# Sheet.net
KiCad netlist of a schematic drawn in Altium Designer
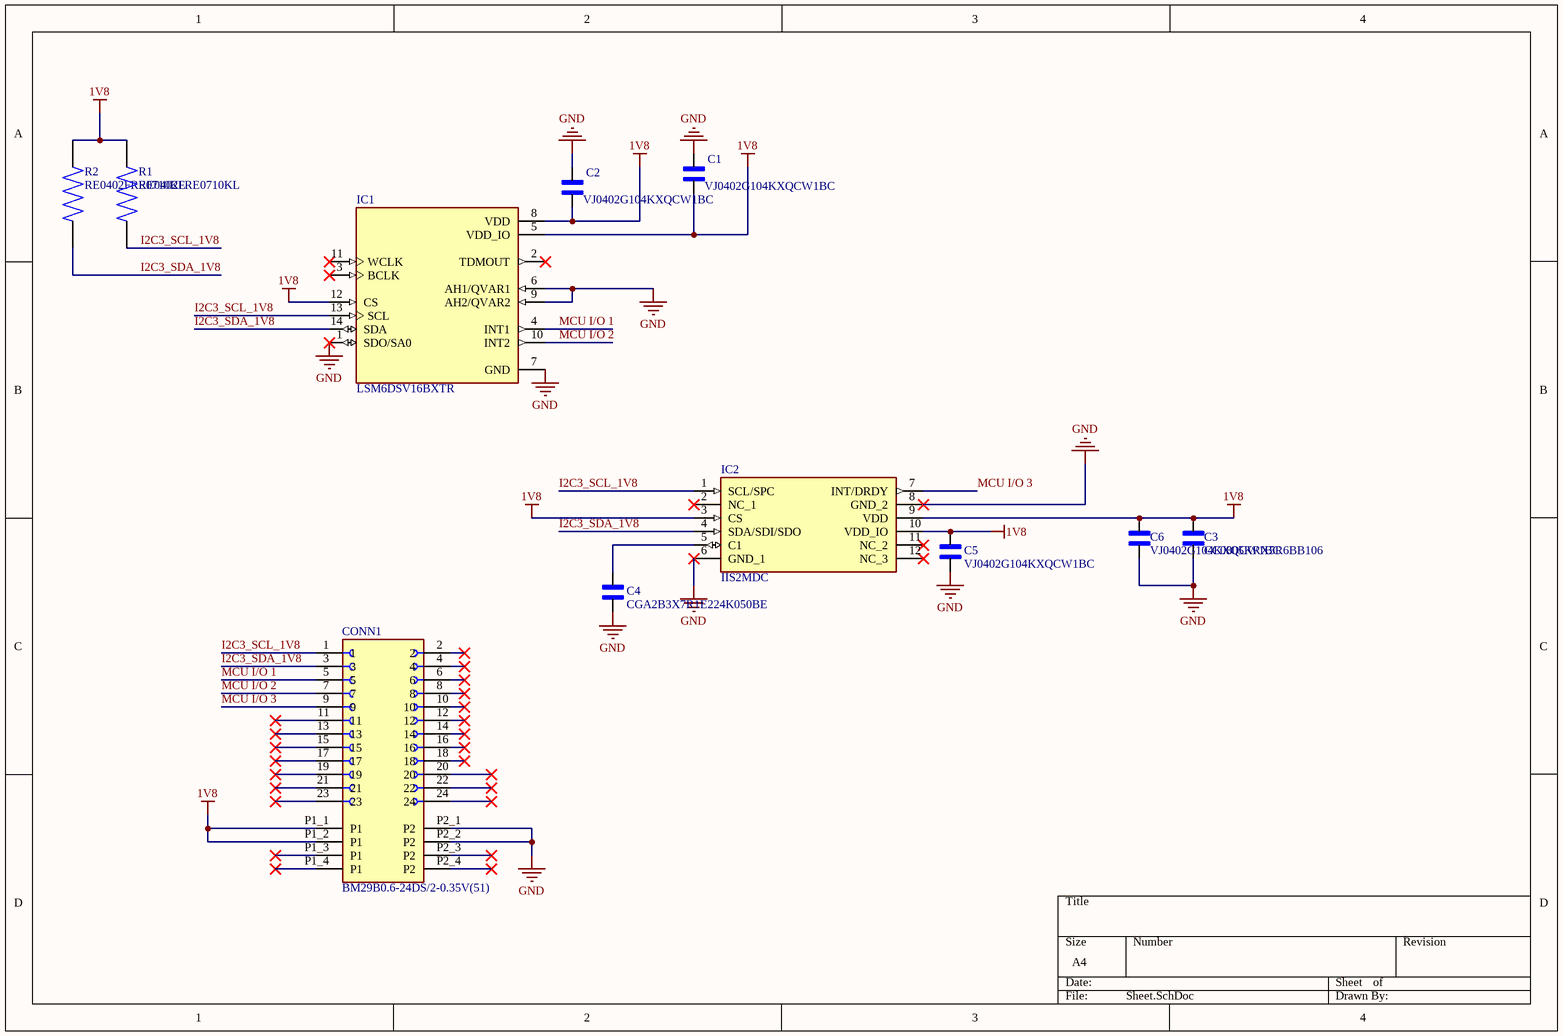
[diagram p0: Sheet.SchDoc]

(export (version "E")
  (design (tool "Eeschema 10.0.6"))
  (components
    (comp (ref "C1")
      (value "VJ0402G104KXQCW1BC")
      (footprint "C100nF - VJ0402G104KXQCW1BC")
      (libsource (lib "Schlib1") (part "VJ0402G104KXQCW1BC"))
    )
    (comp (ref "C2")
      (value "VJ0402G104KXQCW1BC")
      (footprint "C100nF - VJ0402G104KXQCW1BC")
      (libsource (lib "Schlib1") (part "VJ0402G104KXQCW1BC"))
    )
    (comp (ref "C3")
      (value "CC0805KRX5R6BB106")
      (footprint "C10uf - CC0805KRX5R6BB106")
      (libsource (lib "Schlib1") (part "C 10uF"))
    )
    (comp (ref "C4")
      (value "CGA2B3X7R1E224K050BE")
      (footprint "CAPC1005X60N")
      (description "Cap Ceramic 0.22uF 25V X7R 10% Pad SMD 0402 Soft Termination 125C Automotive T/R")
      (fields (field (name "MF") "TDK"))
      (libsource (lib "Schlib1") (part "CGA2B3X7R1E224K050BE"))
    )
    (comp (ref "C5")
      (value "VJ0402G104KXQCW1BC")
      (footprint "C100nF - VJ0402G104KXQCW1BC")
      (libsource (lib "") (part "C 100nf_1"))
    )
    (comp (ref "C6")
      (value "VJ0402G104KXQCW1BC")
      (footprint "C100nF - VJ0402G104KXQCW1BC")
      (libsource (lib "Schlib1") (part "C 100nf"))
    )
    (comp (ref "CONN1")
      (value "BM29B0.6-24DS/2-0.35V(51)")
      (footprint "HRS_BM29B0.6-24DS/2-0.35V(51)")
      (description "26 (24 + 2 Power) Position Connector Receptacle, Center Strip Contacts Surface Mount Gold")
      (fields (field (name "MF") "Hirose Connector"))
      (libsource (lib "Schlib1") (part "BM29B0.6-24DS/2-0.35V(51)"))
    )
    (comp (ref "IC1")
      (value "LSM6DSV16BXTR")
      (footprint "PQFN50P250X300X74-14N")
      (description "Accelerometer, Gyroscope, Temperature, 6 Axis Sensor IÂ²C, I3Câ„ , SPI Output")
      (fields (field (name "MF") "STMicroelectronics"))
      (libsource (lib "Schlib1") (part "LSM6DSV16BXTR"))
    )
    (comp (ref "IC2")
      (value "IIS2MDC")
      (footprint "Magnetometer")
      (libsource (lib "Schlib1") (part "IIS2MDC"))
    )
    (comp (ref "R1")
      (value "RE0402FRE0710KL")
      (footprint "RESC1005X37N")
      (description "10 kOhms Â±1% 0.063W, 1/16W Chip Resistor 0402 (1005 Metric) Moisture Resistant Thick Film")
      (fields (field (name "MF") "Yageo"))
      (libsource (lib "Schlib1") (part "RE0402FRE0710KL"))
    )
    (comp (ref "R2")
      (value "RE0402FRE0710KL")
      (footprint "RESC1005X37N")
      (description "10 kOhms Â±1% 0.063W, 1/16W Chip Resistor 0402 (1005 Metric) Moisture Resistant Thick Film")
      (fields (field (name "MF") "Yageo"))
      (libsource (lib "Schlib1") (part "RE0402FRE0710KL"))
    )
  )
  (nets
    (net (code "1") (name "/I2C3_SCL_1V8") (class "Default")
      (node (ref "CONN1") (pin "1") (pinfunction "1_1") (pintype "passive"))
      (node (ref "IC1") (pin "13") (pinfunction "SCL_13") (pintype "input"))
      (node (ref "IC2") (pin "1") (pinfunction "SCL/SPC_1") (pintype "input"))
      (node (ref "R1") (pin "2") (pinfunction "2_2") (pintype "passive"))
    )
    (net (code "2") (name "/I2C3_SDA_1V8") (class "Default")
      (node (ref "CONN1") (pin "3") (pinfunction "3_3") (pintype "passive"))
      (node (ref "IC1") (pin "14") (pinfunction "SDA_14") (pintype "bidirectional"))
      (node (ref "IC2") (pin "4") (pinfunction "SDA/SDI/SDO_4") (pintype "input"))
      (node (ref "R2") (pin "2") (pinfunction "2_2") (pintype "passive"))
    )
    (net (code "3") (name "/MCU I{slash}O 1") (class "Default")
      (node (ref "CONN1") (pin "5") (pinfunction "5_5") (pintype "passive"))
      (node (ref "IC1") (pin "4") (pinfunction "INT1_4") (pintype "output"))
    )
    (net (code "4") (name "/MCU I{slash}O 2") (class "Default")
      (node (ref "CONN1") (pin "7") (pinfunction "7_7") (pintype "passive"))
      (node (ref "IC1") (pin "10") (pinfunction "INT2_10") (pintype "output"))
    )
    (net (code "5") (name "/MCU I{slash}O 3") (class "Default")
      (node (ref "CONN1") (pin "9") (pinfunction "9_9") (pintype "passive"))
      (node (ref "IC2") (pin "7") (pinfunction "INT/DRDY_7") (pintype "output"))
    )
    (net (code "6") (name "1V8") (class "Default")
      (node (ref "C1") (pin "1") (pinfunction "1_1") (pintype "passive"))
      (node (ref "C2") (pin "1") (pinfunction "1_1") (pintype "passive"))
      (node (ref "C3") (pin "1") (pinfunction "1_1") (pintype "passive"))
      (node (ref "C5") (pin "2") (pinfunction "2_2") (pintype "passive"))
      (node (ref "C6") (pin "1") (pinfunction "1_1") (pintype "passive"))
      (node (ref "CONN1") (pin "P1_1") (pinfunction "P1_P1_1") (pintype "power_in"))
      (node (ref "CONN1") (pin "P1_2") (pinfunction "P1_P1_2") (pintype "power_in"))
      (node (ref "IC1") (pin "12") (pinfunction "CS_12") (pintype "input"))
      (node (ref "IC1") (pin "5") (pinfunction "VDD_IO_5") (pintype "power_in"))
      (node (ref "IC1") (pin "8") (pinfunction "VDD_8") (pintype "power_in"))
      (node (ref "IC2") (pin "10") (pinfunction "VDD_IO_10") (pintype "power_in"))
      (node (ref "IC2") (pin "3") (pinfunction "CS_3") (pintype "input"))
      (node (ref "IC2") (pin "9") (pinfunction "VDD_9") (pintype "power_in"))
      (node (ref "R1") (pin "1") (pinfunction "1_1") (pintype "passive"))
      (node (ref "R2") (pin "1") (pinfunction "1_1") (pintype "passive"))
    )
    (net (code "7") (name "GND") (class "Default")
      (node (ref "C1") (pin "2") (pinfunction "2_2") (pintype "passive"))
      (node (ref "C2") (pin "2") (pinfunction "2_2") (pintype "passive"))
      (node (ref "C3") (pin "2") (pinfunction "2_2") (pintype "passive"))
      (node (ref "C4") (pin "1") (pinfunction "1_1") (pintype "passive"))
      (node (ref "C5") (pin "1") (pinfunction "1_1") (pintype "passive"))
      (node (ref "C6") (pin "2") (pinfunction "2_2") (pintype "passive"))
      (node (ref "CONN1") (pin "P2_1") (pinfunction "P2_P2_1") (pintype "power_in"))
      (node (ref "CONN1") (pin "P2_2") (pinfunction "P2_P2_2") (pintype "power_in"))
      (node (ref "IC1") (pin "1") (pinfunction "SDO/SA0_1") (pintype "bidirectional"))
      (node (ref "IC1") (pin "6") (pinfunction "AH1/QVAR1_6") (pintype "input"))
      (node (ref "IC1") (pin "7") (pinfunction "GND_7") (pintype "power_in"))
      (node (ref "IC1") (pin "9") (pinfunction "AH2/QVAR2_9") (pintype "input"))
      (node (ref "IC2") (pin "6") (pinfunction "GND_1_6") (pintype "power_in"))
      (node (ref "IC2") (pin "8") (pinfunction "GND_2_8") (pintype "power_in"))
    )
    (net (code "8") (name "Net-(IC2-C1)") (class "Default")
      (node (ref "C4") (pin "2") (pinfunction "2_2") (pintype "passive"))
      (node (ref "IC2") (pin "5") (pinfunction "C1_5") (pintype "bidirectional"))
    )
    (net (code "9") (name "unconnected-(CONN1-P1-PadP1_3)") (class "Default")
      (node (ref "CONN1") (pin "P1_3") (pinfunction "P1_P1_3") (pintype "power_in+no_connect"))
    )
    (net (code "10") (name "unconnected-(CONN1-P1-PadP1_4)") (class "Default")
      (node (ref "CONN1") (pin "P1_4") (pinfunction "P1_P1_4") (pintype "power_in+no_connect"))
    )
    (net (code "11") (name "unconnected-(CONN1-P2-PadP2_3)") (class "Default")
      (node (ref "CONN1") (pin "P2_3") (pinfunction "P2_P2_3") (pintype "power_in+no_connect"))
    )
    (net (code "12") (name "unconnected-(CONN1-P2-PadP2_4)") (class "Default")
      (node (ref "CONN1") (pin "P2_4") (pinfunction "P2_P2_4") (pintype "power_in+no_connect"))
    )
    (net (code "13") (name "unconnected-(CONN1-Pad2)") (class "Default")
      (node (ref "CONN1") (pin "2") (pinfunction "2_2") (pintype "passive+no_connect"))
    )
    (net (code "14") (name "unconnected-(CONN1-Pad4)") (class "Default")
      (node (ref "CONN1") (pin "4") (pinfunction "4_4") (pintype "passive+no_connect"))
    )
    (net (code "15") (name "unconnected-(CONN1-Pad6)") (class "Default")
      (node (ref "CONN1") (pin "6") (pinfunction "6_6") (pintype "passive+no_connect"))
    )
    (net (code "16") (name "unconnected-(CONN1-Pad8)") (class "Default")
      (node (ref "CONN1") (pin "8") (pinfunction "8_8") (pintype "passive+no_connect"))
    )
    (net (code "17") (name "unconnected-(CONN1-Pad10)") (class "Default")
      (node (ref "CONN1") (pin "10") (pinfunction "10_10") (pintype "passive+no_connect"))
    )
    (net (code "18") (name "unconnected-(CONN1-Pad11)") (class "Default")
      (node (ref "CONN1") (pin "11") (pinfunction "11_11") (pintype "passive+no_connect"))
    )
    (net (code "19") (name "unconnected-(CONN1-Pad12)") (class "Default")
      (node (ref "CONN1") (pin "12") (pinfunction "12_12") (pintype "passive+no_connect"))
    )
    (net (code "20") (name "unconnected-(CONN1-Pad13)") (class "Default")
      (node (ref "CONN1") (pin "13") (pinfunction "13_13") (pintype "passive+no_connect"))
    )
    (net (code "21") (name "unconnected-(CONN1-Pad14)") (class "Default")
      (node (ref "CONN1") (pin "14") (pinfunction "14_14") (pintype "passive+no_connect"))
    )
    (net (code "22") (name "unconnected-(CONN1-Pad15)") (class "Default")
      (node (ref "CONN1") (pin "15") (pinfunction "15_15") (pintype "passive+no_connect"))
    )
    (net (code "23") (name "unconnected-(CONN1-Pad16)") (class "Default")
      (node (ref "CONN1") (pin "16") (pinfunction "16_16") (pintype "passive+no_connect"))
    )
    (net (code "24") (name "unconnected-(CONN1-Pad17)") (class "Default")
      (node (ref "CONN1") (pin "17") (pinfunction "17_17") (pintype "passive+no_connect"))
    )
    (net (code "25") (name "unconnected-(CONN1-Pad18)") (class "Default")
      (node (ref "CONN1") (pin "18") (pinfunction "18_18") (pintype "passive+no_connect"))
    )
    (net (code "26") (name "unconnected-(CONN1-Pad19)") (class "Default")
      (node (ref "CONN1") (pin "19") (pinfunction "19_19") (pintype "passive+no_connect"))
    )
    (net (code "27") (name "unconnected-(CONN1-Pad20)") (class "Default")
      (node (ref "CONN1") (pin "20") (pinfunction "20_20") (pintype "passive+no_connect"))
    )
    (net (code "28") (name "unconnected-(CONN1-Pad21)") (class "Default")
      (node (ref "CONN1") (pin "21") (pinfunction "21_21") (pintype "passive+no_connect"))
    )
    (net (code "29") (name "unconnected-(CONN1-Pad22)") (class "Default")
      (node (ref "CONN1") (pin "22") (pinfunction "22_22") (pintype "passive+no_connect"))
    )
    (net (code "30") (name "unconnected-(CONN1-Pad23)") (class "Default")
      (node (ref "CONN1") (pin "23") (pinfunction "23_23") (pintype "passive+no_connect"))
    )
    (net (code "31") (name "unconnected-(CONN1-Pad24)") (class "Default")
      (node (ref "CONN1") (pin "24") (pinfunction "24_24") (pintype "passive+no_connect"))
    )
    (net (code "32") (name "unconnected-(IC1-BCLK-Pad3)") (class "Default")
      (node (ref "IC1") (pin "3") (pinfunction "BCLK_3") (pintype "input+no_connect"))
    )
    (net (code "33") (name "unconnected-(IC1-TDMOUT-Pad2)") (class "Default")
      (node (ref "IC1") (pin "2") (pinfunction "TDMOUT_2") (pintype "output+no_connect"))
    )
    (net (code "34") (name "unconnected-(IC1-WCLK-Pad11)") (class "Default")
      (node (ref "IC1") (pin "11") (pinfunction "WCLK_11") (pintype "input+no_connect"))
    )
    (net (code "35") (name "unconnected-(IC2-NC_1-Pad2)") (class "Default")
      (node (ref "IC2") (pin "2") (pinfunction "NC_1_2") (pintype "tri_state+no_connect"))
    )
    (net (code "36") (name "unconnected-(IC2-NC_2-Pad11)") (class "Default")
      (node (ref "IC2") (pin "11") (pinfunction "NC_2_11") (pintype "tri_state+no_connect"))
    )
    (net (code "37") (name "unconnected-(IC2-NC_3-Pad12)") (class "Default")
      (node (ref "IC2") (pin "12") (pinfunction "NC_3_12") (pintype "tri_state+no_connect"))
    )
  )
)
